# ZHSD-USB-OTG.net
KiCad netlist of a schematic drawn in Altium Designer
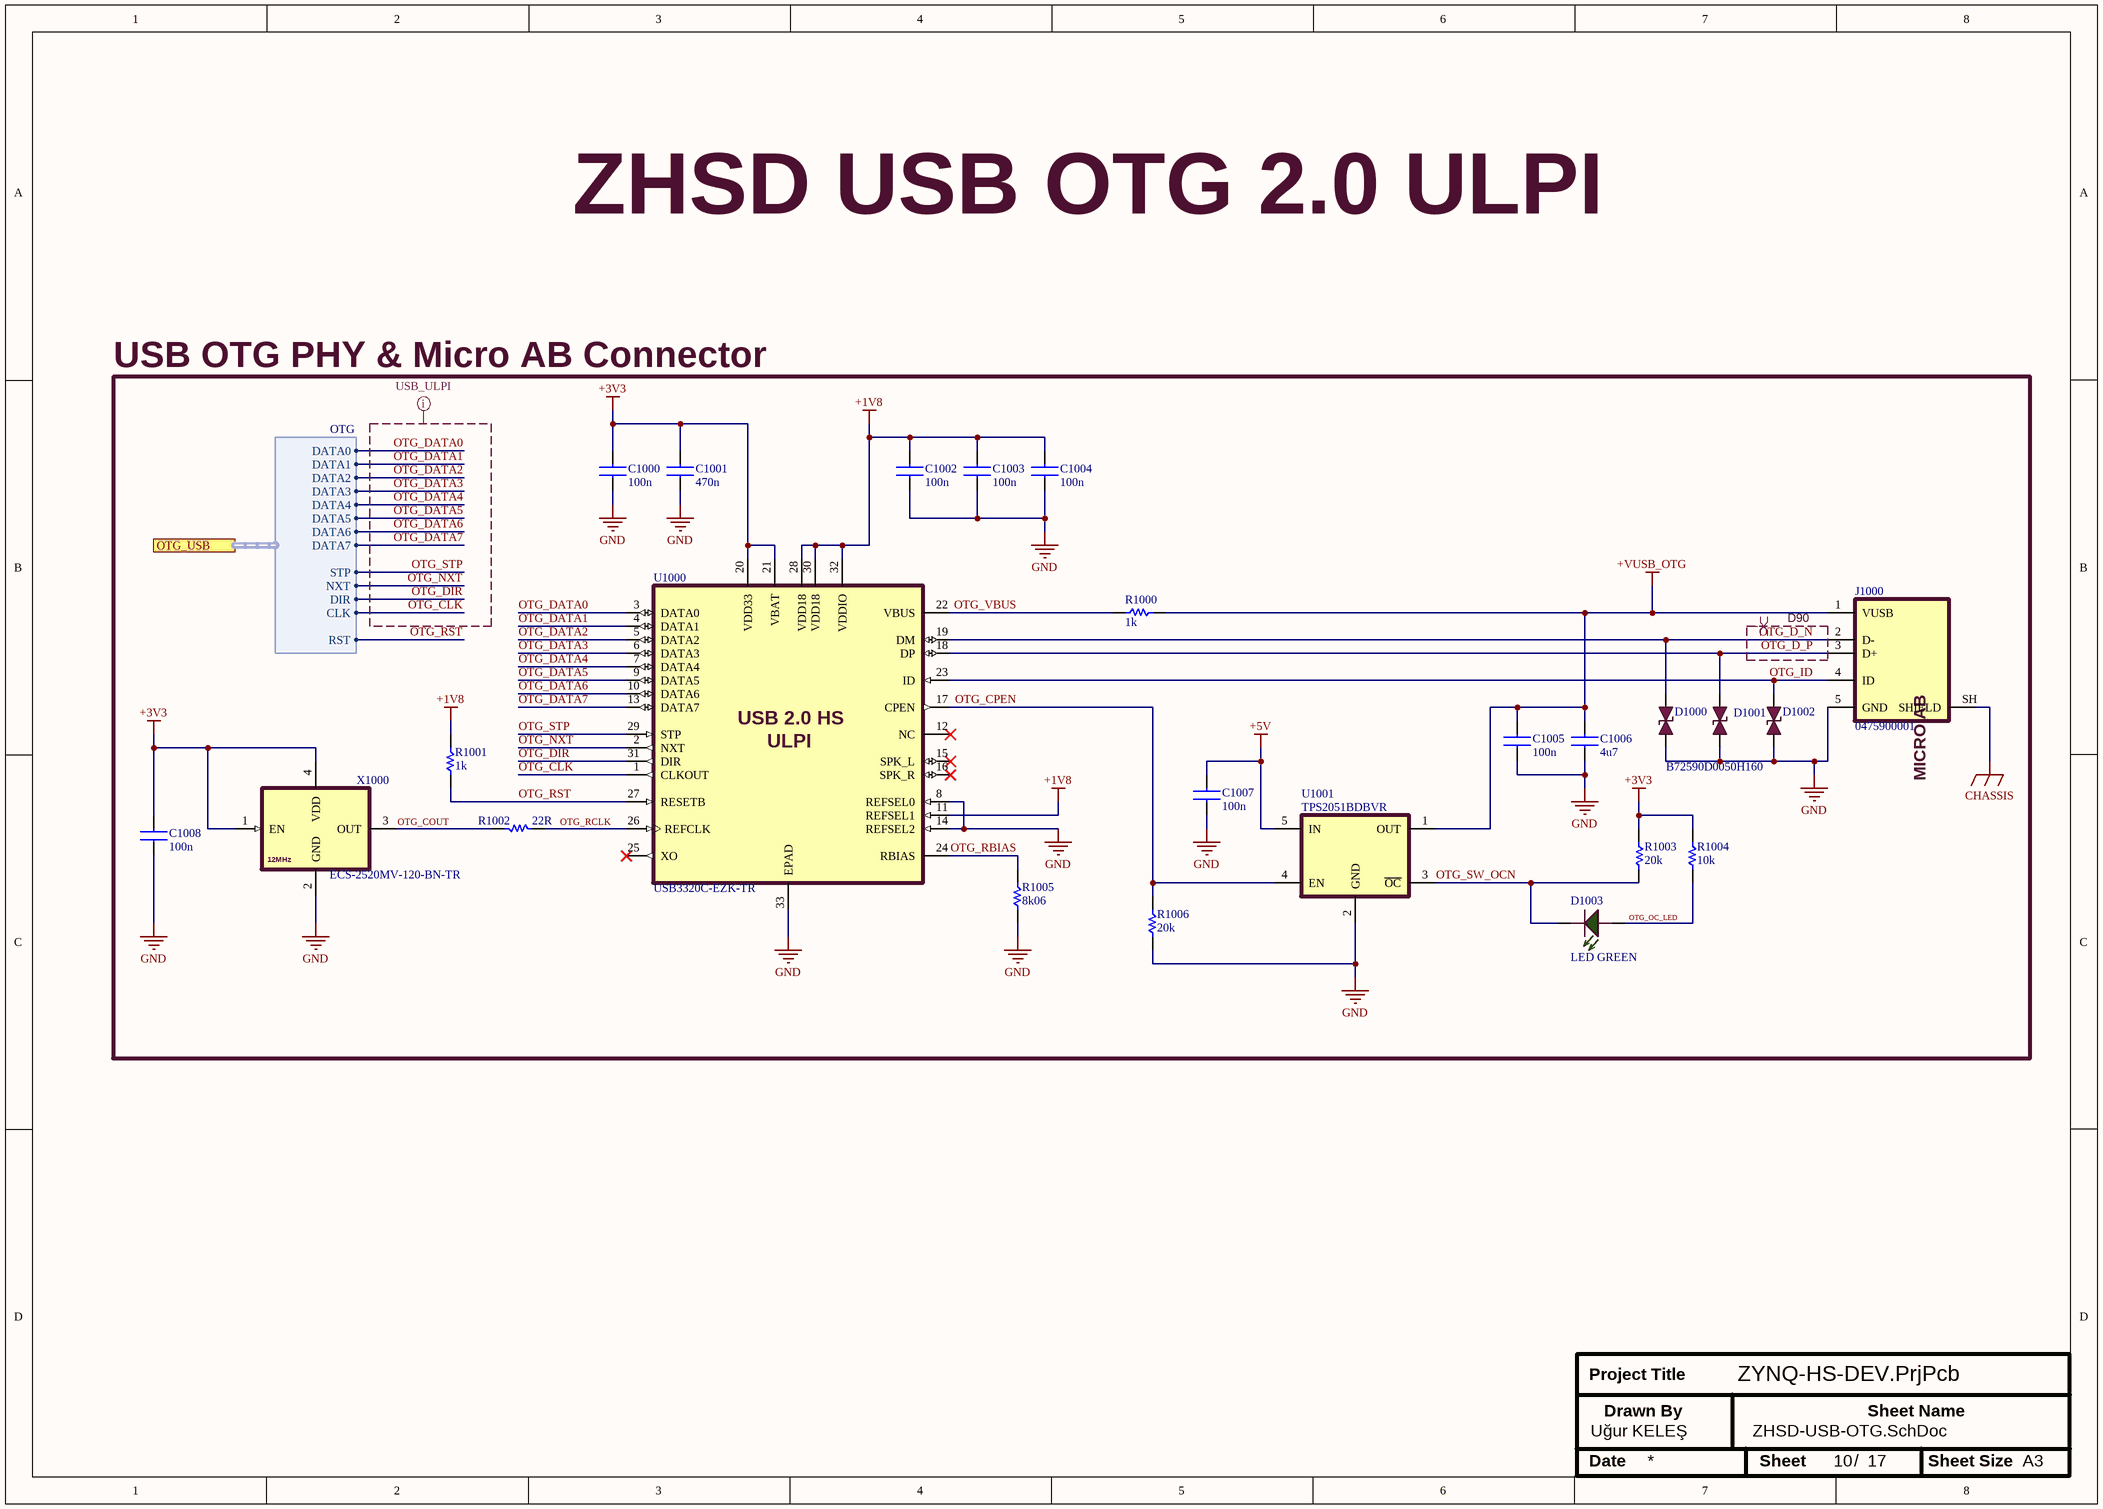
[diagram p0: ZHSD-USB-OTG.SchDoc]

(export (version "E")
  (design (tool "Eeschema 10.0.6"))
  (components
    (comp (ref "C1000")
      (value "100n")
      (footprint "0603CAPC1608X09N")
      (description "CAP CER 0.1UF 16V X7R 0402 (1005) ±10%")
      (fields (field (name "MANUFACTURER") "Murata Electronics") (field (name "MPN") "GRM155R71C104KA88J"))
      (libsource (lib "UK_Library") (part "GRM155R71C104KA88J"))
    )
    (comp (ref "C1001")
      (value "470n")
      (footprint "0402CAPC1005X06N")
      (description "CAP CER 0.47UF 6.3V X5R 0402(1005) ±10%")
      (fields (field (name "MANUFACTURER") "Murata Electronics") (field (name "MPN") "GRM155R60J474KE19D"))
      (libsource (lib "UK_Library") (part "GRM155R60J474KE19D"))
    )
    (comp (ref "C1002")
      (value "100n")
      (footprint "0603CAPC1608X09N")
      (description "CAP CER 0.1UF 16V X7R 0402 (1005) ±10%")
      (fields (field (name "MANUFACTURER") "Murata Electronics") (field (name "MPN") "GRM155R71C104KA88J"))
      (libsource (lib "UK_Library") (part "GRM155R71C104KA88J"))
    )
    (comp (ref "C1003")
      (value "100n")
      (footprint "0603CAPC1608X09N")
      (description "CAP CER 0.1UF 16V X7R 0402 (1005) ±10%")
      (fields (field (name "MANUFACTURER") "Murata Electronics") (field (name "MPN") "GRM155R71C104KA88J"))
      (libsource (lib "UK_Library") (part "GRM155R71C104KA88J"))
    )
    (comp (ref "C1004")
      (value "100n")
      (footprint "0603CAPC1608X09N")
      (description "CAP CER 0.1UF 16V X7R 0402 (1005) ±10%")
      (fields (field (name "MANUFACTURER") "Murata Electronics") (field (name "MPN") "GRM155R71C104KA88J"))
      (libsource (lib "UK_Library") (part "GRM155R71C104KA88J"))
    )
    (comp (ref "C1005")
      (value "100n")
      (footprint "0603CAPC1608X09N")
      (description "CAP CER 0.1UF 16V X7R 0402 (1005) ±10%")
      (fields (field (name "MANUFACTURER") "Murata Electronics") (field (name "MPN") "GRM155R71C104KA88J"))
      (libsource (lib "UK_Library") (part "GRM155R71C104KA88J"))
    )
    (comp (ref "C1006")
      (value "4u7")
      (footprint "0603CAPC1608X09N")
      (description "CAP CER 4.7UF 10V X5R 0603 (1608) ±10%")
      (fields
        (field (name "MANUFACTURER") "Samsung Electro-Mechanics")
        (field (name "MPN") "CL10A475KP8NNNC")
      )
      (libsource (lib "UK_Library") (part "CL10A475KP8NNNC"))
    )
    (comp (ref "C1007")
      (value "100n")
      (footprint "0603CAPC1608X09N")
      (description "CAP CER 0.1UF 16V X7R 0402 (1005) ±10%")
      (fields (field (name "MANUFACTURER") "Murata Electronics") (field (name "MPN") "GRM155R71C104KA88J"))
      (libsource (lib "UK_Library") (part "GRM155R71C104KA88J"))
    )
    (comp (ref "C1008")
      (value "100n")
      (footprint "0603CAPC1608X09N")
      (description "CAP CER 0.1UF 50V X7R 0603 (1608) ±10%")
      (fields (field (name "MANUFACTURER") "KEMET") (field (name "MPN") "C0603C104K5RACTU"))
      (libsource (lib "UK_Library") (part "C0603C104K5RACTU"))
    )
    (comp (ref "D1000")
      (value "B72590D0050H160")
      (footprint "0402DIOC1005X06N")
      (description "Varistor 1 Circuit Surface Mount, MLCV 0402 (1005 Metric)")
      (fields (field (name "MANUFACTURER") "EPCOS - TDK Electronics"))
      (libsource (lib "UK_Library") (part "B72590D0050H160"))
    )
    (comp (ref "D1001")
      (value "B72590D0050H160")
      (footprint "0402DIOC1005X06N")
      (description "Varistor 1 Circuit Surface Mount, MLCV 0402 (1005 Metric)")
      (fields (field (name "MANUFACTURER") "EPCOS - TDK Electronics"))
      (libsource (lib "UK_Library") (part "B72590D0050H160"))
    )
    (comp (ref "D1002")
      (value "B72590D0050H160")
      (footprint "0402DIOC1005X06N")
      (description "Varistor 1 Circuit Surface Mount, MLCV 0402 (1005 Metric)")
      (fields (field (name "MANUFACTURER") "EPCOS - TDK Electronics"))
      (libsource (lib "UK_Library") (part "B72590D0050H160"))
    )
    (comp (ref "D1003")
      (value "LED GREEN")
      (footprint "0603_LED_1608N")
      (description "LED GREEN CLEAR CHIP SMD")
      (fields (field (name "MANUFACTURER") "Lite-On Inc.") (field (name "MPN") "LTST-C191TGKT"))
      (libsource (lib "UK_Library") (part "LTST-C191TGKT"))
    )
    (comp (ref "J1000")
      (value "0475900001")
      (footprint "USB2.0 MICRO AB SMD")
      (description "CONN RCPT MICRO USB AB 5P SMD RA")
      (fields (field (name "MANUFACTURER") "Molex"))
      (libsource (lib "UK_Library") (part "USB-MICRO-AB"))
    )
    (comp (ref "R1000")
      (value "1k")
      (footprint "0603RESC1608X05N")
      (description "RES 1K OHM 1% 1/10W 0603 (1608)")
      (fields (field (name "MANUFACTURER") "YAGEO") (field (name "MPN") "RC0603FR-071KL"))
      (libsource (lib "UK_Library") (part "RC0603FR-071KL"))
    )
    (comp (ref "R1001")
      (value "1k")
      (footprint "0603RESC1608X05N")
      (description "RES 1K OHM 1% 1/10W 0603 (1608)")
      (fields (field (name "MANUFACTURER") "YAGEO") (field (name "MPN") "RC0603FR-071KL"))
      (libsource (lib "UK_Library") (part "RC0603FR-071KL"))
    )
    (comp (ref "R1002")
      (value "22R")
      (footprint "0603RESC1608X05N")
      (description "RES 22 OHM 1% 1/10W 0603 (1608)")
      (fields (field (name "MANUFACTURER") "YAGEO") (field (name "MPN") "RC0603FR-0722RL"))
      (libsource (lib "UK_Library") (part "RC0603FR-0722RL"))
    )
    (comp (ref "R1003")
      (value "20k")
      (footprint "0402RESC1005X04N")
      (description "RES 20K OHM 1% 1/16W 0402 (1005)")
      (fields (field (name "MANUFACTURER") "YAGEO") (field (name "MPN") "RC0402FR-0720KL"))
      (libsource (lib "UK_Library") (part "RC0402FR-0720KL"))
    )
    (comp (ref "R1004")
      (value "10k")
      (footprint "0603RESC1608X05N")
      (description "RES 10K OHM 1% 1/10W 0603(1608)")
      (fields (field (name "MANUFACTURER") "YAGEO") (field (name "MPN") "RC0603FR-0710KL"))
      (libsource (lib "UK_Library") (part "RC0603FR-0710KL"))
    )
    (comp (ref "R1005")
      (value "8k06")
      (footprint "0402RESC1005X04N")
      (description "RES 8.06K OHM 1% 1/16W 0402 (1005)")
      (fields (field (name "MANUFACTURER") "YAGEO") (field (name "MPN") "RC0402FR-138K06L"))
      (libsource (lib "UK_Library") (part "RC0402FR-138K06L"))
    )
    (comp (ref "R1006")
      (value "20k")
      (footprint "0402RESC1005X04N")
      (description "RES 20K OHM 1% 1/16W 0402 (1005)")
      (fields (field (name "MANUFACTURER") "YAGEO") (field (name "MPN") "RC0402FR-0720KL"))
      (libsource (lib "UK_Library") (part "RC0402FR-0720KL"))
    )
    (comp (ref "U1000")
      (value "USB3320C-EZK-TR")
      (footprint "QFN50P500X500X100_HS-33N")
      (description "Hi-Speed USB 2.0 ULPI Transceiver")
      (fields (field (name "MANUFACTURER") "Microchip"))
      (libsource (lib "UK_Library") (part "USB3320C-EZK-TR"))
    )
    (comp (ref "U1001")
      (value "TPS2051BDBVR")
      (footprint "SOT95P280X125-5N")
      (description "Power Switch/Driver 1:1 N-Channel 500mA SOT-23-5")
      (fields (field (name "MANUFACTURER") "Texas Instruments"))
      (libsource (lib "UK_Library") (part "TPS2051BDBVR"))
    )
    (comp (ref "X1000")
      (value "ECS-2520MV-120-BN-TR")
      (footprint "XTAL_2520")
      (description "XTAL OSC XO 12.0000MHZ CMOS SMD")
      (fields (field (name "MANUFACTURER") "ECS Inc."))
      (libsource (lib "UK_Library") (part "ECS-2520MV-120-BN-TR"))
    )
  )
  (nets
    (net (code "2") (name "+1V8") (class "Default")
      (node (ref "C1002") (pin "2") (pinfunction "2_2") (pintype "passive"))
      (node (ref "C1003") (pin "2") (pinfunction "2_2") (pintype "passive"))
      (node (ref "C1004") (pin "2") (pinfunction "2_2") (pintype "passive"))
      (node (ref "R1001") (pin "2") (pinfunction "2_2") (pintype "passive"))
      (node (ref "U1000") (pin "11") (pinfunction "REFSEL1_11") (pintype "input"))
      (node (ref "U1000") (pin "28") (pinfunction "VDD18_28") (pintype "power_in"))
      (node (ref "U1000") (pin "30") (pinfunction "VDD18_30") (pintype "power_in"))
      (node (ref "U1000") (pin "32") (pinfunction "VDDIO_32") (pintype "power_in"))
    )
    (net (code "3") (name "+3V3") (class "Default")
      (node (ref "C1000") (pin "2") (pinfunction "2_2") (pintype "passive"))
      (node (ref "C1001") (pin "2") (pinfunction "2_2") (pintype "passive"))
      (node (ref "C1008") (pin "2") (pinfunction "2_2") (pintype "passive"))
      (node (ref "R1003") (pin "1") (pinfunction "1_1") (pintype "passive"))
      (node (ref "R1004") (pin "2") (pinfunction "2_2") (pintype "passive"))
      (node (ref "U1000") (pin "20") (pinfunction "VDD33_20") (pintype "power_in"))
      (node (ref "U1000") (pin "21") (pinfunction "VBAT_21") (pintype "power_in"))
      (node (ref "X1000") (pin "1") (pinfunction "EN_1") (pintype "input"))
      (node (ref "X1000") (pin "4") (pinfunction "VDD_4") (pintype "power_in"))
    )
    (net (code "4") (name "+5V") (class "Default")
      (node (ref "C1007") (pin "2") (pinfunction "2_2") (pintype "passive"))
      (node (ref "U1001") (pin "5") (pinfunction "IN_5") (pintype "passive"))
    )
    (net (code "5") (name "+VUSB_OTG") (class "Default")
      (node (ref "C1005") (pin "2") (pinfunction "2_2") (pintype "passive"))
      (node (ref "C1006") (pin "2") (pinfunction "2_2") (pintype "passive"))
      (node (ref "J1000") (pin "1") (pinfunction "VUSB_1") (pintype "passive"))
      (node (ref "R1000") (pin "2") (pinfunction "2_2") (pintype "passive"))
      (node (ref "U1001") (pin "1") (pinfunction "OUT_1") (pintype "passive"))
    )
    (net (code "6") (name "/OTG_CLK") (class "Default")
      (node (ref "U1000") (pin "1") (pinfunction "CLKOUT_1") (pintype "output"))
    )
    (net (code "7") (name "/OTG_COUT") (class "Default")
      (node (ref "R1002") (pin "2") (pinfunction "2_2") (pintype "passive"))
      (node (ref "X1000") (pin "3") (pinfunction "OUT_3") (pintype "passive"))
    )
    (net (code "8") (name "/OTG_CPEN") (class "Default")
      (node (ref "R1006") (pin "2") (pinfunction "2_2") (pintype "passive"))
      (node (ref "U1000") (pin "17") (pinfunction "CPEN_17") (pintype "output"))
      (node (ref "U1001") (pin "4") (pinfunction "EN_4") (pintype "passive"))
    )
    (net (code "9") (name "/OTG_DATA0") (class "Default")
      (node (ref "U1000") (pin "3") (pinfunction "DATA0_3") (pintype "bidirectional"))
    )
    (net (code "10") (name "/OTG_DATA1") (class "Default")
      (node (ref "U1000") (pin "4") (pinfunction "DATA1_4") (pintype "bidirectional"))
    )
    (net (code "11") (name "/OTG_DATA2") (class "Default")
      (node (ref "U1000") (pin "5") (pinfunction "DATA2_5") (pintype "bidirectional"))
    )
    (net (code "12") (name "/OTG_DATA3") (class "Default")
      (node (ref "U1000") (pin "6") (pinfunction "DATA3_6") (pintype "bidirectional"))
    )
    (net (code "13") (name "/OTG_DATA4") (class "Default")
      (node (ref "U1000") (pin "7") (pinfunction "DATA4_7") (pintype "bidirectional"))
    )
    (net (code "14") (name "/OTG_DATA5") (class "Default")
      (node (ref "U1000") (pin "9") (pinfunction "DATA5_9") (pintype "bidirectional"))
    )
    (net (code "15") (name "/OTG_DATA6") (class "Default")
      (node (ref "U1000") (pin "10") (pinfunction "DATA6_10") (pintype "bidirectional"))
    )
    (net (code "16") (name "/OTG_DATA7") (class "Default")
      (node (ref "U1000") (pin "13") (pinfunction "DATA7_13") (pintype "bidirectional"))
    )
    (net (code "17") (name "/OTG_DIR") (class "Default")
      (node (ref "U1000") (pin "31") (pinfunction "DIR_31") (pintype "output"))
    )
    (net (code "18") (name "/OTG_D_N") (class "Default")
      (node (ref "D1000") (pin "2") (pinfunction "2_2") (pintype "passive"))
      (node (ref "J1000") (pin "2") (pinfunction "D-_2") (pintype "passive"))
      (node (ref "U1000") (pin "19") (pinfunction "DM_19") (pintype "bidirectional"))
    )
    (net (code "19") (name "/OTG_D_P") (class "Default")
      (node (ref "D1001") (pin "2") (pinfunction "2_2") (pintype "passive"))
      (node (ref "J1000") (pin "3") (pinfunction "D+_3") (pintype "passive"))
      (node (ref "U1000") (pin "18") (pinfunction "DP_18") (pintype "bidirectional"))
    )
    (net (code "20") (name "/OTG_ID") (class "Default")
      (node (ref "D1002") (pin "2") (pinfunction "2_2") (pintype "passive"))
      (node (ref "J1000") (pin "4") (pinfunction "ID_4") (pintype "passive"))
      (node (ref "U1000") (pin "23") (pinfunction "ID_23") (pintype "input"))
    )
    (net (code "21") (name "/OTG_NXT") (class "Default")
      (node (ref "U1000") (pin "2") (pinfunction "NXT_2") (pintype "output"))
    )
    (net (code "22") (name "/OTG_OC_LED") (class "Default")
      (node (ref "D1003") (pin "1") (pinfunction "A_1") (pintype "passive"))
      (node (ref "R1004") (pin "1") (pinfunction "1_1") (pintype "passive"))
    )
    (net (code "23") (name "/OTG_RBIAS") (class "Default")
      (node (ref "R1005") (pin "2") (pinfunction "2_2") (pintype "passive"))
      (node (ref "U1000") (pin "24") (pinfunction "RBIAS_24") (pintype "passive"))
    )
    (net (code "24") (name "/OTG_RCLK") (class "Default")
      (node (ref "R1002") (pin "1") (pinfunction "1_1") (pintype "passive"))
      (node (ref "U1000") (pin "26") (pinfunction "REFCLK_26") (pintype "input"))
    )
    (net (code "25") (name "/OTG_RST") (class "Default")
      (node (ref "R1001") (pin "1") (pinfunction "1_1") (pintype "passive"))
      (node (ref "U1000") (pin "27") (pinfunction "RESETB_27") (pintype "input"))
    )
    (net (code "26") (name "/OTG_STP") (class "Default")
      (node (ref "U1000") (pin "29") (pinfunction "STP_29") (pintype "input"))
    )
    (net (code "27") (name "/OTG_SW_OCN") (class "Default")
      (node (ref "D1003") (pin "2") (pinfunction "C_2") (pintype "passive"))
      (node (ref "R1003") (pin "2") (pinfunction "2_2") (pintype "passive"))
      (node (ref "U1001") (pin "3") (pinfunction "OC_3") (pintype "passive"))
    )
    (net (code "28") (name "/OTG_VBUS") (class "Default")
      (node (ref "R1000") (pin "1") (pinfunction "1_1") (pintype "passive"))
      (node (ref "U1000") (pin "22") (pinfunction "VBUS_22") (pintype "power_in"))
    )
    (net (code "30") (name "CHASSIS") (class "Default")
      (node (ref "J1000") (pin "SH") (pinfunction "SHIELD_SH") (pintype "passive"))
    )
    (net (code "31") (name "GND") (class "Default")
      (node (ref "C1000") (pin "1") (pinfunction "1_1") (pintype "passive"))
      (node (ref "C1001") (pin "1") (pinfunction "1_1") (pintype "passive"))
      (node (ref "C1002") (pin "1") (pinfunction "1_1") (pintype "passive"))
      (node (ref "C1003") (pin "1") (pinfunction "1_1") (pintype "passive"))
      (node (ref "C1004") (pin "1") (pinfunction "1_1") (pintype "passive"))
      (node (ref "C1005") (pin "1") (pinfunction "1_1") (pintype "passive"))
      (node (ref "C1006") (pin "1") (pinfunction "1_1") (pintype "passive"))
      (node (ref "C1007") (pin "1") (pinfunction "1_1") (pintype "passive"))
      (node (ref "C1008") (pin "1") (pinfunction "1_1") (pintype "passive"))
      (node (ref "D1000") (pin "1") (pinfunction "1_1") (pintype "passive"))
      (node (ref "D1001") (pin "1") (pinfunction "1_1") (pintype "passive"))
      (node (ref "D1002") (pin "1") (pinfunction "1_1") (pintype "passive"))
      (node (ref "J1000") (pin "5") (pinfunction "GND_5") (pintype "passive"))
      (node (ref "R1005") (pin "1") (pinfunction "1_1") (pintype "passive"))
      (node (ref "R1006") (pin "1") (pinfunction "1_1") (pintype "passive"))
      (node (ref "U1000") (pin "14") (pinfunction "REFSEL2_14") (pintype "input"))
      (node (ref "U1000") (pin "33") (pinfunction "EPAD_33") (pintype "power_in"))
      (node (ref "U1000") (pin "8") (pinfunction "REFSEL0_8") (pintype "input"))
      (node (ref "U1001") (pin "2") (pinfunction "GND_2") (pintype "passive"))
      (node (ref "X1000") (pin "2") (pinfunction "GND_2") (pintype "power_in"))
    )
    (net (code "32") (name "unconnected-(U1000-NC-Pad12)") (class "Default")
      (node (ref "U1000") (pin "12") (pinfunction "NC_12") (pintype "passive+no_connect"))
    )
    (net (code "33") (name "unconnected-(U1000-SPK_L-Pad15)") (class "Default")
      (node (ref "U1000") (pin "15") (pinfunction "SPK_L_15") (pintype "bidirectional+no_connect"))
    )
    (net (code "34") (name "unconnected-(U1000-SPK_R-Pad16)") (class "Default")
      (node (ref "U1000") (pin "16") (pinfunction "SPK_R_16") (pintype "bidirectional+no_connect"))
    )
    (net (code "35") (name "unconnected-(U1000-XO-Pad25)") (class "Default")
      (node (ref "U1000") (pin "25") (pinfunction "XO_25") (pintype "output+no_connect"))
    )
  )
)
